# ATA.net
KiCad netlist of a schematic drawn in EAGLE
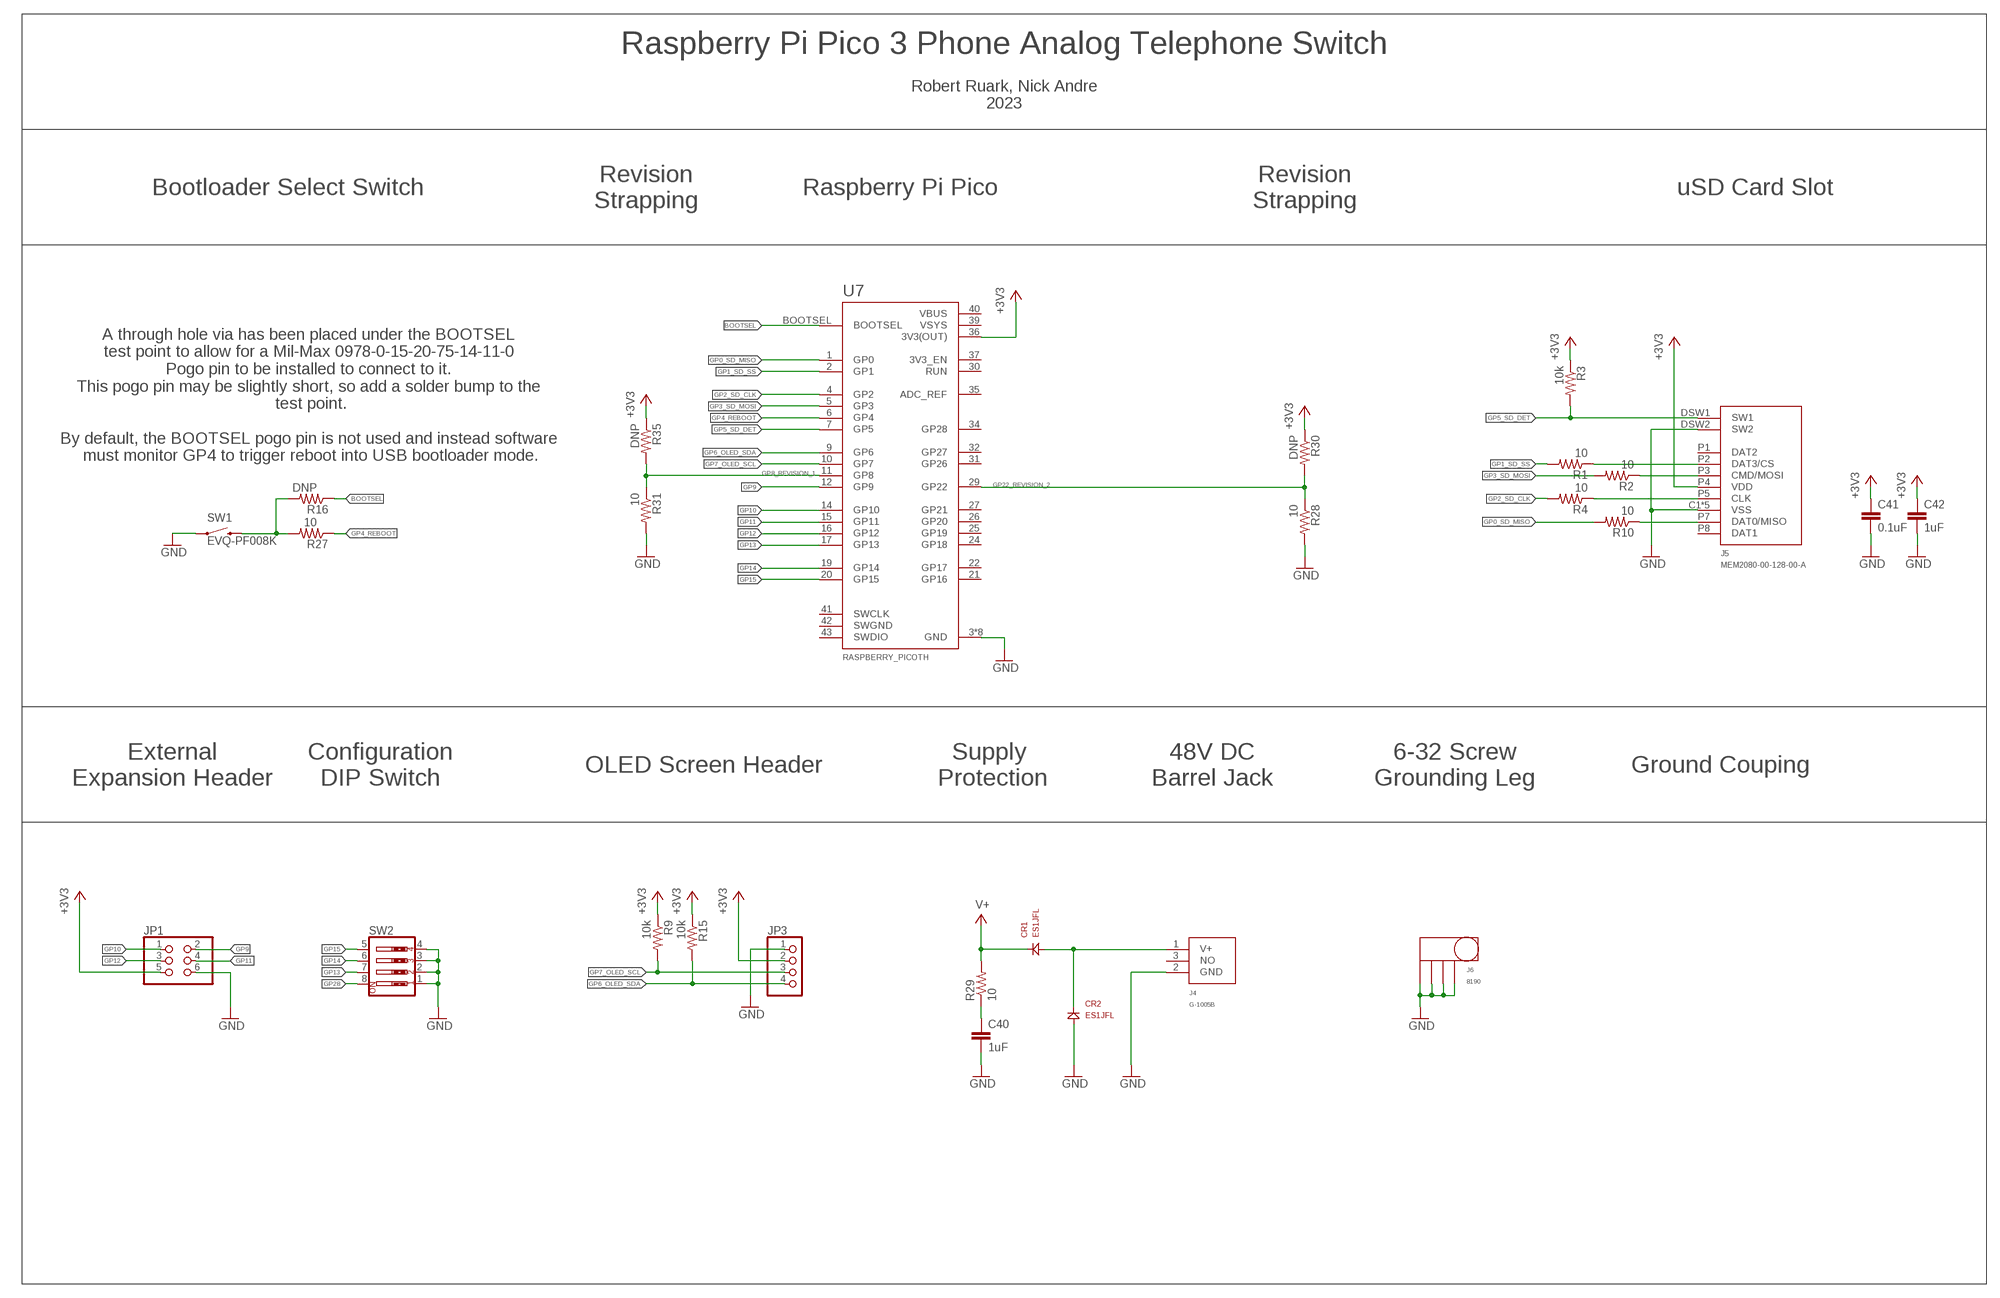
[diagram p0: schematic, sheet 1]
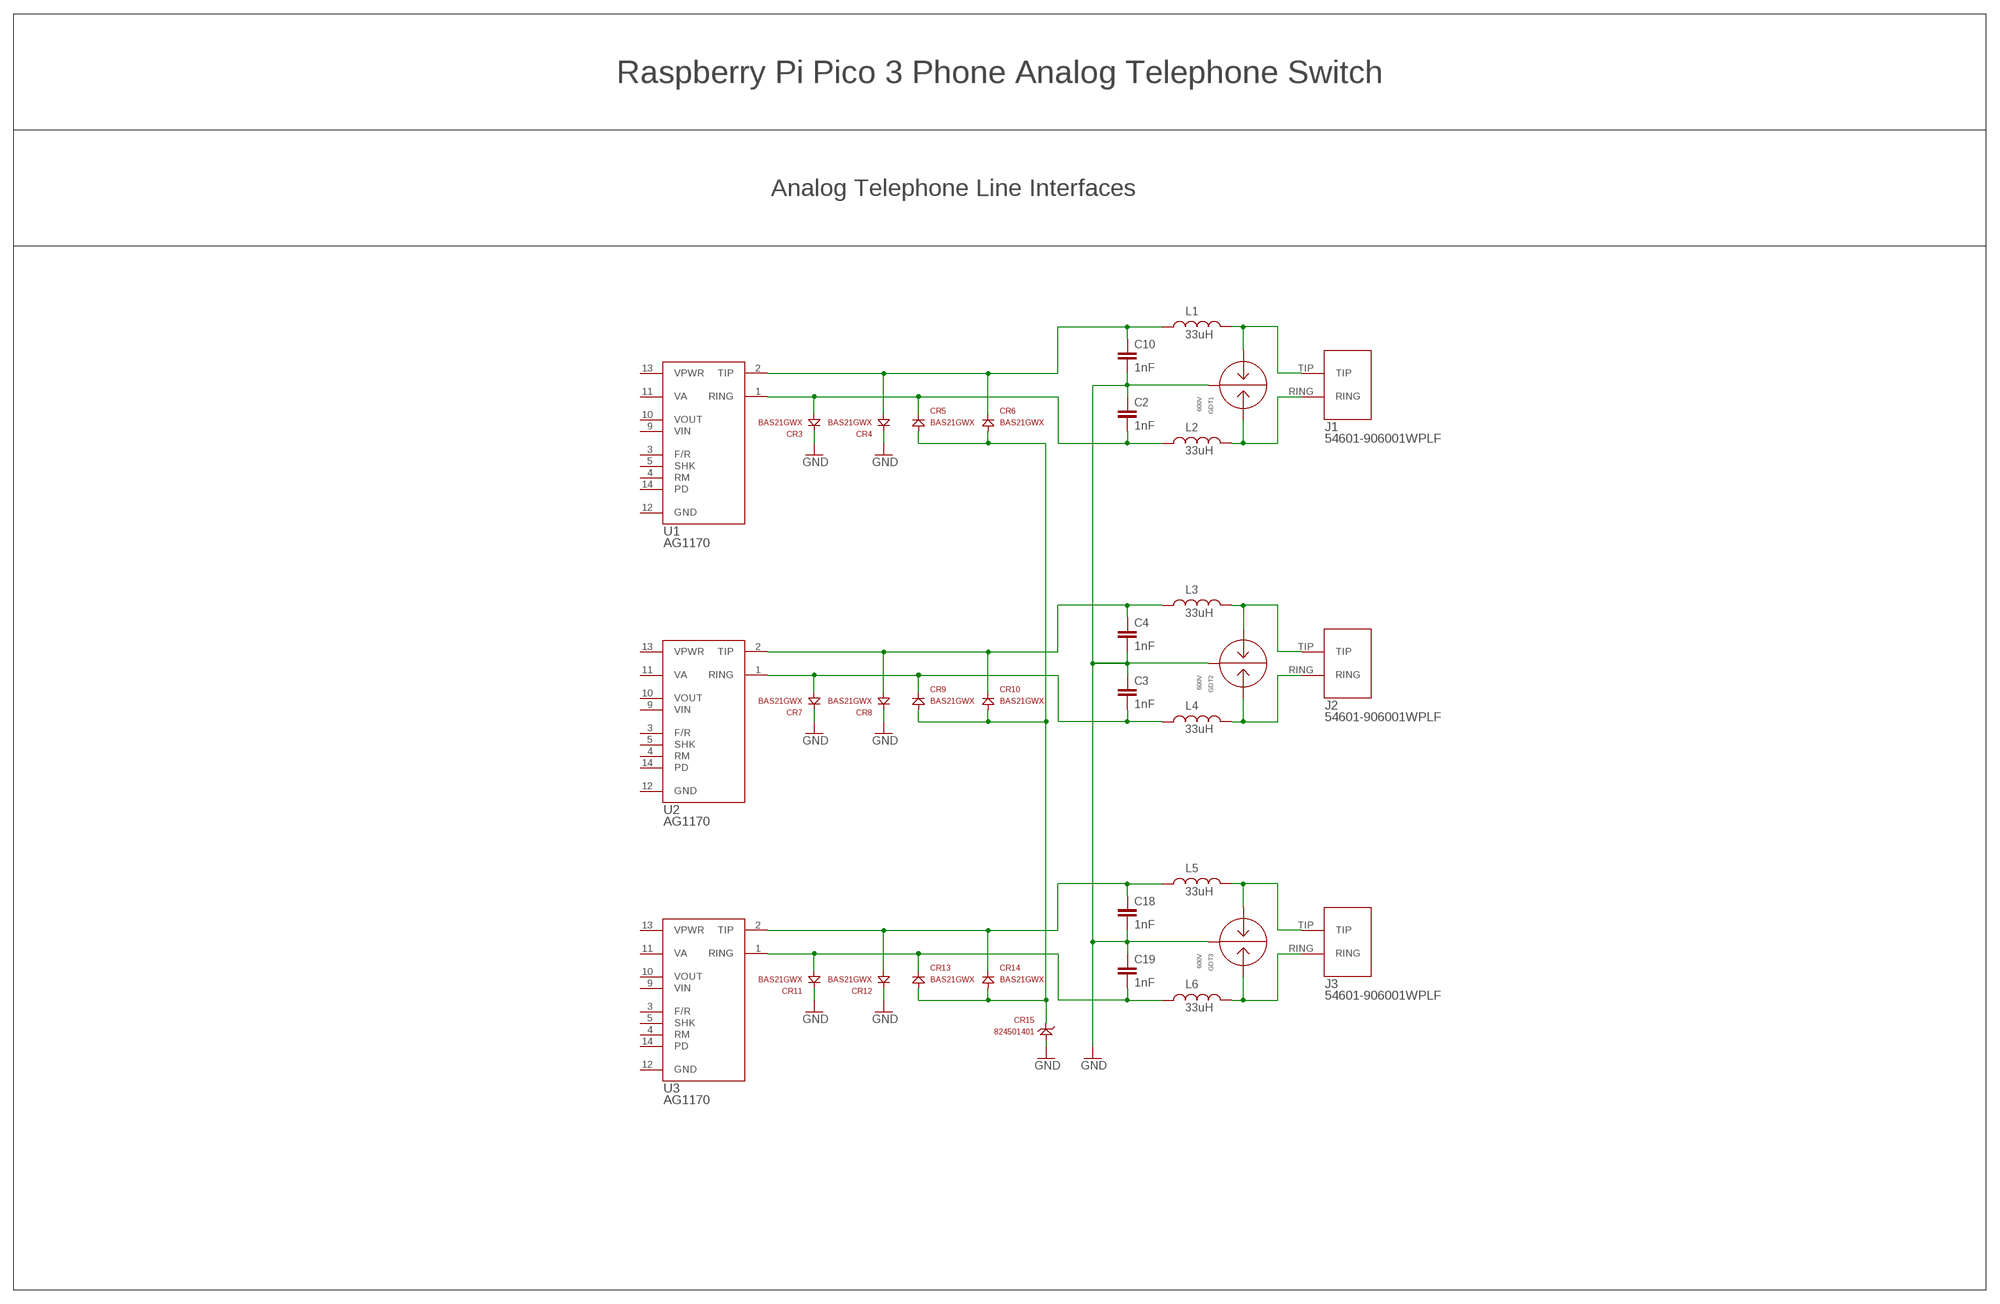
[diagram p1: schematic, sheet 2]

(export (version "E")
  (design (tool "Eeschema 10.0.6"))
  (components
    (comp (ref "C40")
      (value "1uF")
      (footprint "eagle-import:1206")
      (libsource (lib "eagle-import") (part "1206_CAPACITOR"))
    )
    (comp (ref "C41")
      (value "0.1uF")
      (footprint "eagle-import:0603")
      (libsource (lib "eagle-import") (part "0603_CAPACITOR"))
    )
    (comp (ref "C42")
      (value "1uF")
      (footprint "eagle-import:0805")
      (libsource (lib "eagle-import") (part "0805_CAPACITOR"))
    )
    (comp (ref "CR1")
      (value "ES1JFL")
      (footprint "eagle-import:SOD123(AK)")
      (fields (field (name "PARTNO") "ES1JFLCT-ND"))
      (libsource (lib "eagle-import") (part "ES1JFL"))
    )
    (comp (ref "CR2")
      (value "ES1JFL")
      (footprint "eagle-import:SOD123(AK)")
      (fields (field (name "PARTNO") "ES1JFLCT-ND"))
      (libsource (lib "eagle-import") (part "ES1JFL"))
    )
    (comp (ref "J4")
      (value "G-1005B")
      (footprint "eagle-import:G-1005B")
      (fields (field (name "PARTNO") "1939-G-1005B-ND"))
      (libsource (lib "eagle-import") (part "G-1005B"))
    )
    (comp (ref "J5")
      (value "MEM2080-00-128-00-A")
      (footprint "eagle-import:MEM2080")
      (fields (field (name "PARTNO") "2073-MEM2080-00-128-00-ACT-ND"))
      (libsource (lib "eagle-import") (part "MEM2080-00-128-00-A"))
    )
    (comp (ref "J6")
      (value "8190")
      (footprint "eagle-import:7781")
      (fields (field (name "PARTNO") "36-8190-ND"))
      (libsource (lib "eagle-import") (part "8190"))
    )
    (comp (ref "JP1")
      (value "PINHD-2X3/90")
      (footprint "eagle-import:2X03_90")
      (libsource (lib "eagle-import") (part "PINHD-2X3/90"))
    )
    (comp (ref "JP3")
      (value "PINHD-1X4")
      (footprint "eagle-import:1X04")
      (libsource (lib "eagle-import") (part "PINHD-1X4"))
    )
    (comp (ref "R1")
      (value "10")
      (footprint "eagle-import:0603")
      (libsource (lib "eagle-import") (part "0603_RESISTOR"))
    )
    (comp (ref "R2")
      (value "10")
      (footprint "eagle-import:0603")
      (libsource (lib "eagle-import") (part "0603_RESISTOR"))
    )
    (comp (ref "R3")
      (value "10k")
      (footprint "eagle-import:0603")
      (libsource (lib "eagle-import") (part "0603_RESISTOR"))
    )
    (comp (ref "R4")
      (value "10")
      (footprint "eagle-import:0603")
      (libsource (lib "eagle-import") (part "0603_RESISTOR"))
    )
    (comp (ref "R9")
      (value "10k")
      (footprint "eagle-import:0603")
      (libsource (lib "eagle-import") (part "0603_RESISTOR"))
    )
    (comp (ref "R10")
      (value "10")
      (footprint "eagle-import:0603")
      (libsource (lib "eagle-import") (part "0603_RESISTOR"))
    )
    (comp (ref "R15")
      (value "10k")
      (footprint "eagle-import:0603")
      (libsource (lib "eagle-import") (part "0603_RESISTOR"))
    )
    (comp (ref "R16")
      (value "DNP")
      (footprint "eagle-import:0603")
      (libsource (lib "eagle-import") (part "0603_RESISTOR"))
    )
    (comp (ref "R27")
      (value "10")
      (footprint "eagle-import:0603")
      (libsource (lib "eagle-import") (part "0603_RESISTOR"))
    )
    (comp (ref "R28")
      (value "10")
      (footprint "eagle-import:0603")
      (libsource (lib "eagle-import") (part "0603_RESISTOR"))
    )
    (comp (ref "R29")
      (value "10")
      (footprint "eagle-import:1206")
      (libsource (lib "eagle-import") (part "1206_RESISTOR"))
    )
    (comp (ref "R30")
      (value "DNP")
      (footprint "eagle-import:0603")
      (libsource (lib "eagle-import") (part "0603_RESISTOR"))
    )
    (comp (ref "R31")
      (value "10")
      (footprint "eagle-import:0603")
      (libsource (lib "eagle-import") (part "0603_RESISTOR"))
    )
    (comp (ref "R35")
      (value "DNP")
      (footprint "eagle-import:0603")
      (libsource (lib "eagle-import") (part "0603_RESISTOR"))
    )
    (comp (ref "SW1")
      (value "EVQ-PF008K")
      (footprint "eagle-import:EVQ-PF008K")
      (fields (field (name "PARTNO") "P10880S-ND"))
      (libsource (lib "eagle-import") (part "EVQ-PF008K"))
    )
    (comp (ref "SW2")
      (value "SW_DIP-4")
      (footprint "eagle-import:EDG-04")
      (libsource (lib "eagle-import") (part "SW_DIP-4"))
    )
    (comp (ref "U7")
      (value "RASPBERRY_PICOTH")
      (footprint "eagle-import:PICO-PKG-TH")
      (libsource (lib "eagle-import") (part "RASPBERRY_PICOTH"))
    )
    (comp (ref "C2")
      (value "1nF")
      (footprint "eagle-import:0805")
      (libsource (lib "eagle-import") (part "0805_CAPACITOR"))
    )
    (comp (ref "C3")
      (value "1nF")
      (footprint "eagle-import:0805")
      (libsource (lib "eagle-import") (part "0805_CAPACITOR"))
    )
    (comp (ref "C4")
      (value "1nF")
      (footprint "eagle-import:0805")
      (libsource (lib "eagle-import") (part "0805_CAPACITOR"))
    )
    (comp (ref "C10")
      (value "1nF")
      (footprint "eagle-import:0805")
      (libsource (lib "eagle-import") (part "0805_CAPACITOR"))
    )
    (comp (ref "C18")
      (value "1nF")
      (footprint "eagle-import:0805")
      (libsource (lib "eagle-import") (part "0805_CAPACITOR"))
    )
    (comp (ref "C19")
      (value "1nF")
      (footprint "eagle-import:0805")
      (libsource (lib "eagle-import") (part "0805_CAPACITOR"))
    )
    (comp (ref "CR3")
      (value "BAS21GWX")
      (footprint "eagle-import:SOD123")
      (fields (field (name "PARTNO") "1727-7323-1-ND"))
      (libsource (lib "eagle-import") (part "BAS21GWX"))
    )
    (comp (ref "CR4")
      (value "BAS21GWX")
      (footprint "eagle-import:SOD123")
      (fields (field (name "PARTNO") "1727-7323-1-ND"))
      (libsource (lib "eagle-import") (part "BAS21GWX"))
    )
    (comp (ref "CR5")
      (value "BAS21GWX")
      (footprint "eagle-import:SOD123")
      (fields (field (name "PARTNO") "1727-7323-1-ND"))
      (libsource (lib "eagle-import") (part "BAS21GWX"))
    )
    (comp (ref "CR6")
      (value "BAS21GWX")
      (footprint "eagle-import:SOD123")
      (fields (field (name "PARTNO") "1727-7323-1-ND"))
      (libsource (lib "eagle-import") (part "BAS21GWX"))
    )
    (comp (ref "CR7")
      (value "BAS21GWX")
      (footprint "eagle-import:SOD123")
      (fields (field (name "PARTNO") "1727-7323-1-ND"))
      (libsource (lib "eagle-import") (part "BAS21GWX"))
    )
    (comp (ref "CR8")
      (value "BAS21GWX")
      (footprint "eagle-import:SOD123")
      (fields (field (name "PARTNO") "1727-7323-1-ND"))
      (libsource (lib "eagle-import") (part "BAS21GWX"))
    )
    (comp (ref "CR9")
      (value "BAS21GWX")
      (footprint "eagle-import:SOD123")
      (fields (field (name "PARTNO") "1727-7323-1-ND"))
      (libsource (lib "eagle-import") (part "BAS21GWX"))
    )
    (comp (ref "CR10")
      (value "BAS21GWX")
      (footprint "eagle-import:SOD123")
      (fields (field (name "PARTNO") "1727-7323-1-ND"))
      (libsource (lib "eagle-import") (part "BAS21GWX"))
    )
    (comp (ref "CR11")
      (value "BAS21GWX")
      (footprint "eagle-import:SOD123")
      (fields (field (name "PARTNO") "1727-7323-1-ND"))
      (libsource (lib "eagle-import") (part "BAS21GWX"))
    )
    (comp (ref "CR12")
      (value "BAS21GWX")
      (footprint "eagle-import:SOD123")
      (fields (field (name "PARTNO") "1727-7323-1-ND"))
      (libsource (lib "eagle-import") (part "BAS21GWX"))
    )
    (comp (ref "CR13")
      (value "BAS21GWX")
      (footprint "eagle-import:SOD123")
      (fields (field (name "PARTNO") "1727-7323-1-ND"))
      (libsource (lib "eagle-import") (part "BAS21GWX"))
    )
    (comp (ref "CR14")
      (value "BAS21GWX")
      (footprint "eagle-import:SOD123")
      (fields (field (name "PARTNO") "1727-7323-1-ND"))
      (libsource (lib "eagle-import") (part "BAS21GWX"))
    )
    (comp (ref "CR15")
      (value "824501401")
      (footprint "eagle-import:DO-214AC")
      (fields (field (name "PARTNO") "732-9960-1-ND"))
      (libsource (lib "eagle-import") (part "824501401"))
    )
    (comp (ref "GDT1")
      (value "600V")
      (footprint "eagle-import:2036_GDT")
      (fields (field (name "PARTNO") "2036-60-SM-RPLFCT-ND"))
      (libsource (lib "eagle-import") (part "2036-60-SM-RPLF"))
    )
    (comp (ref "GDT2")
      (value "600V")
      (footprint "eagle-import:2036_GDT")
      (fields (field (name "PARTNO") "2036-60-SM-RPLFCT-ND"))
      (libsource (lib "eagle-import") (part "2036-60-SM-RPLF"))
    )
    (comp (ref "GDT3")
      (value "600V")
      (footprint "eagle-import:2036_GDT")
      (fields (field (name "PARTNO") "2036-60-SM-RPLFCT-ND"))
      (libsource (lib "eagle-import") (part "2036-60-SM-RPLF"))
    )
    (comp (ref "J1")
      (value "54601-906001WPLF")
      (footprint "eagle-import:54601-906001WPLF")
      (fields (field (name "PARTNO") "609-5354-ND"))
      (libsource (lib "eagle-import") (part "54601-906001WPLF"))
    )
    (comp (ref "J2")
      (value "54601-906001WPLF")
      (footprint "eagle-import:54601-906001WPLF")
      (fields (field (name "PARTNO") "609-5354-ND"))
      (libsource (lib "eagle-import") (part "54601-906001WPLF"))
    )
    (comp (ref "J3")
      (value "54601-906001WPLF")
      (footprint "eagle-import:54601-906001WPLF")
      (fields (field (name "PARTNO") "609-5354-ND"))
      (libsource (lib "eagle-import") (part "54601-906001WPLF"))
    )
    (comp (ref "L1")
      (value "33uH")
      (footprint "eagle-import:SDR0403")
      (fields (field (name "PARTNO") "SDR0403-330KLCT-ND"))
      (libsource (lib "eagle-import") (part "SDR0403-330KL"))
    )
    (comp (ref "L2")
      (value "33uH")
      (footprint "eagle-import:SDR0403")
      (fields (field (name "PARTNO") "SDR0403-330KLCT-ND"))
      (libsource (lib "eagle-import") (part "SDR0403-330KL"))
    )
    (comp (ref "L3")
      (value "33uH")
      (footprint "eagle-import:SDR0403")
      (fields (field (name "PARTNO") "SDR0403-330KLCT-ND"))
      (libsource (lib "eagle-import") (part "SDR0403-330KL"))
    )
    (comp (ref "L4")
      (value "33uH")
      (footprint "eagle-import:SDR0403")
      (fields (field (name "PARTNO") "SDR0403-330KLCT-ND"))
      (libsource (lib "eagle-import") (part "SDR0403-330KL"))
    )
    (comp (ref "L5")
      (value "33uH")
      (footprint "eagle-import:SDR0403")
      (fields (field (name "PARTNO") "SDR0403-330KLCT-ND"))
      (libsource (lib "eagle-import") (part "SDR0403-330KL"))
    )
    (comp (ref "L6")
      (value "33uH")
      (footprint "eagle-import:SDR0403")
      (fields (field (name "PARTNO") "SDR0403-330KLCT-ND"))
      (libsource (lib "eagle-import") (part "SDR0403-330KL"))
    )
    (comp (ref "U1")
      (value "AG1170")
      (footprint "eagle-import:AG1170S")
      (libsource (lib "eagle-import") (part "AG1170"))
    )
    (comp (ref "U2")
      (value "AG1170")
      (footprint "eagle-import:AG1170S")
      (libsource (lib "eagle-import") (part "AG1170"))
    )
    (comp (ref "U3")
      (value "AG1170")
      (footprint "eagle-import:AG1170S")
      (libsource (lib "eagle-import") (part "AG1170"))
    )
  )
  (nets
    (net (code "1") (name "+3V3") (class "Default")
      (node (ref "C41") (pin "1") (pinfunction "1_1") (pintype "passive"))
      (node (ref "C42") (pin "1") (pinfunction "1_1") (pintype "passive"))
      (node (ref "J5") (pin "P4") (pinfunction "VDD_P4") (pintype "bidirectional"))
      (node (ref "JP1") (pin "5") (pinfunction "5_5") (pintype "passive"))
      (node (ref "JP3") (pin "2") (pinfunction "2_2") (pintype "passive"))
      (node (ref "R15") (pin "1") (pinfunction "1_1") (pintype "passive"))
      (node (ref "R3") (pin "1") (pinfunction "1_1") (pintype "passive"))
      (node (ref "R30") (pin "1") (pinfunction "1_1") (pintype "passive"))
      (node (ref "R35") (pin "1") (pinfunction "1_1") (pintype "passive"))
      (node (ref "R9") (pin "1") (pinfunction "1_1") (pintype "passive"))
      (node (ref "U7") (pin "36") (pinfunction "3V3(OUT)_36") (pintype "power_in"))
    )
    (net (code "2") (name "BOOTSEL") (class "Default")
      (node (ref "R16") (pin "1") (pinfunction "1_1") (pintype "passive"))
      (node (ref "U7") (pin "BOOTSEL") (pinfunction "BOOTSEL_BOOTSEL") (pintype "bidirectional"))
    )
    (net (code "3") (name "GND") (class "Default")
      (node (ref "C10") (pin "2") (pinfunction "2_2") (pintype "passive"))
      (node (ref "C18") (pin "2") (pinfunction "2_2") (pintype "passive"))
      (node (ref "C19") (pin "1") (pinfunction "1_1") (pintype "passive"))
      (node (ref "C2") (pin "1") (pinfunction "1_1") (pintype "passive"))
      (node (ref "C3") (pin "1") (pinfunction "1_1") (pintype "passive"))
      (node (ref "C4") (pin "2") (pinfunction "2_2") (pintype "passive"))
      (node (ref "C40") (pin "2") (pinfunction "2_2") (pintype "passive"))
      (node (ref "C41") (pin "2") (pinfunction "2_2") (pintype "passive"))
      (node (ref "C42") (pin "2") (pinfunction "2_2") (pintype "passive"))
      (node (ref "CR11") (pin "1") (pinfunction "K_1") (pintype "bidirectional"))
      (node (ref "CR12") (pin "1") (pinfunction "K_1") (pintype "bidirectional"))
      (node (ref "CR15") (pin "A") (pinfunction "A_A") (pintype "bidirectional"))
      (node (ref "CR2") (pin "A") (pinfunction "A_A") (pintype "bidirectional"))
      (node (ref "CR3") (pin "1") (pinfunction "K_1") (pintype "bidirectional"))
      (node (ref "CR4") (pin "1") (pinfunction "K_1") (pintype "bidirectional"))
      (node (ref "CR7") (pin "1") (pinfunction "K_1") (pintype "bidirectional"))
      (node (ref "CR8") (pin "1") (pinfunction "K_1") (pintype "bidirectional"))
      (node (ref "GDT1") (pin "C") (pinfunction "C_C") (pintype "bidirectional"))
      (node (ref "GDT2") (pin "C") (pinfunction "C_C") (pintype "bidirectional"))
      (node (ref "GDT3") (pin "C") (pinfunction "C_C") (pintype "bidirectional"))
      (node (ref "J4") (pin "2") (pinfunction "GND_2") (pintype "bidirectional"))
      (node (ref "J5") (pin "C1") (pinfunction "VSS_C1") (pintype "bidirectional"))
      (node (ref "J5") (pin "C2") (pinfunction "VSS_C2") (pintype "bidirectional"))
      (node (ref "J5") (pin "C3") (pinfunction "VSS_C3") (pintype "bidirectional"))
      (node (ref "J5") (pin "C4") (pinfunction "VSS_C4") (pintype "bidirectional"))
      (node (ref "J5") (pin "DSW2") (pinfunction "SW2_DSW2") (pintype "bidirectional"))
      (node (ref "J5") (pin "P6") (pinfunction "VSS_P6") (pintype "bidirectional"))
      (node (ref "J6") (pin "P$1") (pinfunction "P$1_P$1") (pintype "bidirectional"))
      (node (ref "J6") (pin "P$2") (pinfunction "P$2_P$2") (pintype "bidirectional"))
      (node (ref "J6") (pin "P$3") (pinfunction "P$3_P$3") (pintype "bidirectional"))
      (node (ref "J6") (pin "P$4") (pinfunction "P$4_P$4") (pintype "bidirectional"))
      (node (ref "JP1") (pin "6") (pinfunction "6_6") (pintype "passive"))
      (node (ref "JP3") (pin "1") (pinfunction "1_1") (pintype "passive"))
      (node (ref "R28") (pin "2") (pinfunction "2_2") (pintype "passive"))
      (node (ref "R31") (pin "2") (pinfunction "2_2") (pintype "passive"))
      (node (ref "SW1") (pin "S1") (pinfunction "1_S1") (pintype "passive"))
      (node (ref "SW2") (pin "1") (pinfunction "1_1") (pintype "passive"))
      (node (ref "SW2") (pin "2") (pinfunction "2_2") (pintype "passive"))
      (node (ref "SW2") (pin "3") (pinfunction "3_3") (pintype "passive"))
      (node (ref "SW2") (pin "4") (pinfunction "4_4") (pintype "passive"))
      (node (ref "U7") (pin "13") (pinfunction "GND_13") (pintype "power_in"))
      (node (ref "U7") (pin "18") (pinfunction "GND_18") (pintype "power_in"))
      (node (ref "U7") (pin "23") (pinfunction "GND_23") (pintype "power_in"))
      (node (ref "U7") (pin "28") (pinfunction "GND_28") (pintype "power_in"))
      (node (ref "U7") (pin "3") (pinfunction "GND_3") (pintype "power_in"))
      (node (ref "U7") (pin "33") (pinfunction "GND_33") (pintype "power_in"))
      (node (ref "U7") (pin "38") (pinfunction "GND_38") (pintype "power_in"))
      (node (ref "U7") (pin "8") (pinfunction "GND_8") (pintype "power_in"))
    )
    (net (code "4") (name "GP0_SD_MISO") (class "Default")
      (node (ref "R10") (pin "2") (pinfunction "2_2") (pintype "passive"))
      (node (ref "U7") (pin "1") (pinfunction "GP0_1") (pintype "bidirectional"))
    )
    (net (code "5") (name "GP1_SD_SS") (class "Default")
      (node (ref "R1") (pin "2") (pinfunction "2_2") (pintype "passive"))
      (node (ref "U7") (pin "2") (pinfunction "GP1_2") (pintype "bidirectional"))
    )
    (net (code "6") (name "GP2_SD_CLK") (class "Default")
      (node (ref "R4") (pin "2") (pinfunction "2_2") (pintype "passive"))
      (node (ref "U7") (pin "4") (pinfunction "GP2_4") (pintype "bidirectional"))
    )
    (net (code "7") (name "GP3_SD_MOSI") (class "Default")
      (node (ref "R2") (pin "2") (pinfunction "2_2") (pintype "passive"))
      (node (ref "U7") (pin "5") (pinfunction "GP3_5") (pintype "bidirectional"))
    )
    (net (code "8") (name "GP4_REBOOT") (class "Default")
      (node (ref "R27") (pin "1") (pinfunction "1_1") (pintype "passive"))
      (node (ref "U7") (pin "6") (pinfunction "GP4_6") (pintype "bidirectional"))
    )
    (net (code "9") (name "GP5_SD_DET") (class "Default")
      (node (ref "J5") (pin "DSW1") (pinfunction "SW1_DSW1") (pintype "bidirectional"))
      (node (ref "R3") (pin "2") (pinfunction "2_2") (pintype "passive"))
      (node (ref "U7") (pin "7") (pinfunction "GP5_7") (pintype "bidirectional"))
    )
    (net (code "10") (name "GP6_OLED_SDA") (class "Default")
      (node (ref "JP3") (pin "4") (pinfunction "4_4") (pintype "passive"))
      (node (ref "R15") (pin "2") (pinfunction "2_2") (pintype "passive"))
      (node (ref "U7") (pin "9") (pinfunction "GP6_9") (pintype "bidirectional"))
    )
    (net (code "11") (name "GP7_OLED_SCL") (class "Default")
      (node (ref "JP3") (pin "3") (pinfunction "3_3") (pintype "passive"))
      (node (ref "R9") (pin "2") (pinfunction "2_2") (pintype "passive"))
      (node (ref "U7") (pin "10") (pinfunction "GP7_10") (pintype "bidirectional"))
    )
    (net (code "12") (name "GP8_REVISION_1") (class "Default")
      (node (ref "R31") (pin "1") (pinfunction "1_1") (pintype "passive"))
      (node (ref "R35") (pin "2") (pinfunction "2_2") (pintype "passive"))
      (node (ref "U7") (pin "11") (pinfunction "GP8_11") (pintype "bidirectional"))
    )
    (net (code "13") (name "GP9") (class "Default")
      (node (ref "JP1") (pin "2") (pinfunction "2_2") (pintype "passive"))
      (node (ref "U7") (pin "12") (pinfunction "GP9_12") (pintype "bidirectional"))
    )
    (net (code "14") (name "GP10") (class "Default")
      (node (ref "JP1") (pin "1") (pinfunction "1_1") (pintype "passive"))
      (node (ref "U7") (pin "14") (pinfunction "GP10_14") (pintype "bidirectional"))
    )
    (net (code "15") (name "GP11") (class "Default")
      (node (ref "JP1") (pin "4") (pinfunction "4_4") (pintype "passive"))
      (node (ref "U7") (pin "15") (pinfunction "GP11_15") (pintype "bidirectional"))
    )
    (net (code "16") (name "GP12") (class "Default")
      (node (ref "JP1") (pin "3") (pinfunction "3_3") (pintype "passive"))
      (node (ref "U7") (pin "16") (pinfunction "GP12_16") (pintype "bidirectional"))
    )
    (net (code "17") (name "GP13") (class "Default")
      (node (ref "SW2") (pin "7") (pinfunction "7_7") (pintype "passive"))
      (node (ref "U7") (pin "17") (pinfunction "GP13_17") (pintype "bidirectional"))
    )
    (net (code "18") (name "GP14") (class "Default")
      (node (ref "SW2") (pin "6") (pinfunction "6_6") (pintype "passive"))
      (node (ref "U7") (pin "19") (pinfunction "GP14_19") (pintype "bidirectional"))
    )
    (net (code "19") (name "GP15") (class "Default")
      (node (ref "SW2") (pin "5") (pinfunction "5_5") (pintype "passive"))
      (node (ref "U7") (pin "20") (pinfunction "GP15_20") (pintype "bidirectional"))
    )
    (net (code "20") (name "GP22_REVISION_2") (class "Default")
      (node (ref "R28") (pin "1") (pinfunction "1_1") (pintype "passive"))
      (node (ref "R30") (pin "2") (pinfunction "2_2") (pintype "passive"))
      (node (ref "U7") (pin "29") (pinfunction "GP22_29") (pintype "bidirectional"))
    )
    (net (code "21") (name "GP28") (class "Default")
      (node (ref "SW2") (pin "8") (pinfunction "8_8") (pintype "passive"))
    )
    (net (code "22") (name "Net-(C40-Pad1)") (class "Default")
      (node (ref "C40") (pin "1") (pinfunction "1_1") (pintype "passive"))
      (node (ref "R29") (pin "1") (pinfunction "1_1") (pintype "passive"))
    )
    (net (code "23") (name "Net-(CR3-A)") (class "Default")
      (node (ref "C2") (pin "2") (pinfunction "2_2") (pintype "passive"))
      (node (ref "CR3") (pin "2") (pinfunction "A_2") (pintype "bidirectional"))
      (node (ref "CR5") (pin "1") (pinfunction "K_1") (pintype "bidirectional"))
      (node (ref "L2") (pin "1") (pinfunction "P$1_1") (pintype "bidirectional"))
      (node (ref "U1") (pin "1") (pinfunction "RING_1") (pintype "bidirectional"))
    )
    (net (code "24") (name "Net-(CR4-A)") (class "Default")
      (node (ref "C10") (pin "1") (pinfunction "1_1") (pintype "passive"))
      (node (ref "CR4") (pin "2") (pinfunction "A_2") (pintype "bidirectional"))
      (node (ref "CR6") (pin "1") (pinfunction "K_1") (pintype "bidirectional"))
      (node (ref "L1") (pin "1") (pinfunction "P$1_1") (pintype "bidirectional"))
      (node (ref "U1") (pin "2") (pinfunction "TIP_2") (pintype "bidirectional"))
    )
    (net (code "25") (name "Net-(CR7-A)") (class "Default")
      (node (ref "C3") (pin "2") (pinfunction "2_2") (pintype "passive"))
      (node (ref "CR7") (pin "2") (pinfunction "A_2") (pintype "bidirectional"))
      (node (ref "CR9") (pin "1") (pinfunction "K_1") (pintype "bidirectional"))
      (node (ref "L4") (pin "1") (pinfunction "P$1_1") (pintype "bidirectional"))
      (node (ref "U2") (pin "1") (pinfunction "RING_1") (pintype "bidirectional"))
    )
    (net (code "26") (name "Net-(CR10-A)") (class "Default")
      (node (ref "CR10") (pin "2") (pinfunction "A_2") (pintype "bidirectional"))
      (node (ref "CR13") (pin "2") (pinfunction "A_2") (pintype "bidirectional"))
      (node (ref "CR14") (pin "2") (pinfunction "A_2") (pintype "bidirectional"))
      (node (ref "CR15") (pin "C") (pinfunction "K_C") (pintype "bidirectional"))
      (node (ref "CR5") (pin "2") (pinfunction "A_2") (pintype "bidirectional"))
      (node (ref "CR6") (pin "2") (pinfunction "A_2") (pintype "bidirectional"))
      (node (ref "CR9") (pin "2") (pinfunction "A_2") (pintype "bidirectional"))
    )
    (net (code "27") (name "Net-(CR10-K)") (class "Default")
      (node (ref "C4") (pin "1") (pinfunction "1_1") (pintype "passive"))
      (node (ref "CR10") (pin "1") (pinfunction "K_1") (pintype "bidirectional"))
      (node (ref "CR8") (pin "2") (pinfunction "A_2") (pintype "bidirectional"))
      (node (ref "L3") (pin "1") (pinfunction "P$1_1") (pintype "bidirectional"))
      (node (ref "U2") (pin "2") (pinfunction "TIP_2") (pintype "bidirectional"))
    )
    (net (code "28") (name "Net-(CR11-A)") (class "Default")
      (node (ref "C19") (pin "2") (pinfunction "2_2") (pintype "passive"))
      (node (ref "CR11") (pin "2") (pinfunction "A_2") (pintype "bidirectional"))
      (node (ref "CR13") (pin "1") (pinfunction "K_1") (pintype "bidirectional"))
      (node (ref "L6") (pin "1") (pinfunction "P$1_1") (pintype "bidirectional"))
      (node (ref "U3") (pin "1") (pinfunction "RING_1") (pintype "bidirectional"))
    )
    (net (code "29") (name "Net-(CR12-A)") (class "Default")
      (node (ref "C18") (pin "1") (pinfunction "1_1") (pintype "passive"))
      (node (ref "CR12") (pin "2") (pinfunction "A_2") (pintype "bidirectional"))
      (node (ref "CR14") (pin "1") (pinfunction "K_1") (pintype "bidirectional"))
      (node (ref "L5") (pin "1") (pinfunction "P$1_1") (pintype "bidirectional"))
      (node (ref "U3") (pin "2") (pinfunction "TIP_2") (pintype "bidirectional"))
    )
    (net (code "30") (name "Net-(J4-V+)") (class "Default")
      (node (ref "CR1") (pin "A") (pinfunction "A_A") (pintype "bidirectional"))
      (node (ref "CR2") (pin "K") (pinfunction "K_K") (pintype "bidirectional"))
      (node (ref "J4") (pin "1") (pinfunction "V+_1") (pintype "bidirectional"))
    )
    (net (code "31") (name "Net-(J5-CLK)") (class "Default")
      (node (ref "J5") (pin "P5") (pinfunction "CLK_P5") (pintype "bidirectional"))
      (node (ref "R4") (pin "1") (pinfunction "1_1") (pintype "passive"))
    )
    (net (code "32") (name "Net-(J5-CMD{slash}MOSI)") (class "Default")
      (node (ref "J5") (pin "P3") (pinfunction "CMD/MOSI_P3") (pintype "bidirectional"))
      (node (ref "R2") (pin "1") (pinfunction "1_1") (pintype "passive"))
    )
    (net (code "33") (name "Net-(J5-DAT0{slash}MISO)") (class "Default")
      (node (ref "J5") (pin "P7") (pinfunction "DAT0/MISO_P7") (pintype "bidirectional"))
      (node (ref "R10") (pin "1") (pinfunction "1_1") (pintype "passive"))
    )
    (net (code "34") (name "Net-(J5-DAT3{slash}CS)") (class "Default")
      (node (ref "J5") (pin "P2") (pinfunction "DAT3/CS_P2") (pintype "bidirectional"))
      (node (ref "R1") (pin "1") (pinfunction "1_1") (pintype "passive"))
    )
    (net (code "35") (name "Net-(L1-P$2)") (class "Default")
      (node (ref "GDT1") (pin "L1") (pinfunction "L1_L1") (pintype "bidirectional"))
      (node (ref "J1") (pin "TIP") (pinfunction "TIP_TIP") (pintype "bidirectional"))
      (node (ref "L1") (pin "2") (pinfunction "P$2_2") (pintype "bidirectional"))
    )
    (net (code "36") (name "Net-(L2-P$2)") (class "Default")
      (node (ref "GDT1") (pin "L2") (pinfunction "L2_L2") (pintype "bidirectional"))
      (node (ref "J1") (pin "RING") (pinfunction "RING_RING") (pintype "bidirectional"))
      (node (ref "L2") (pin "2") (pinfunction "P$2_2") (pintype "bidirectional"))
    )
    (net (code "37") (name "Net-(L3-P$2)") (class "Default")
      (node (ref "GDT2") (pin "L1") (pinfunction "L1_L1") (pintype "bidirectional"))
      (node (ref "J2") (pin "TIP") (pinfunction "TIP_TIP") (pintype "bidirectional"))
      (node (ref "L3") (pin "2") (pinfunction "P$2_2") (pintype "bidirectional"))
    )
    (net (code "38") (name "Net-(L4-P$2)") (class "Default")
      (node (ref "GDT2") (pin "L2") (pinfunction "L2_L2") (pintype "bidirectional"))
      (node (ref "J2") (pin "RING") (pinfunction "RING_RING") (pintype "bidirectional"))
      (node (ref "L4") (pin "2") (pinfunction "P$2_2") (pintype "bidirectional"))
    )
    (net (code "39") (name "Net-(L5-P$2)") (class "Default")
      (node (ref "GDT3") (pin "L1") (pinfunction "L1_L1") (pintype "bidirectional"))
      (node (ref "J3") (pin "TIP") (pinfunction "TIP_TIP") (pintype "bidirectional"))
      (node (ref "L5") (pin "2") (pinfunction "P$2_2") (pintype "bidirectional"))
    )
    (net (code "40") (name "Net-(L6-P$2)") (class "Default")
      (node (ref "GDT3") (pin "L2") (pinfunction "L2_L2") (pintype "bidirectional"))
      (node (ref "J3") (pin "RING") (pinfunction "RING_RING") (pintype "bidirectional"))
      (node (ref "L6") (pin "2") (pinfunction "P$2_2") (pintype "bidirectional"))
    )
    (net (code "41") (name "Net-(SW1-2)") (class "Default")
      (node (ref "R16") (pin "2") (pinfunction "2_2") (pintype "passive"))
      (node (ref "R27") (pin "2") (pinfunction "2_2") (pintype "passive"))
      (node (ref "SW1") (pin "S2") (pinfunction "2_S2") (pintype "passive"))
    )
    (net (code "42") (name "SWGND") (class "Default")
      (node (ref "U7") (pin "42") (pinfunction "SWGND_42") (pintype "power_in"))
    )
    (net (code "43") (name "V+") (class "Default")
      (node (ref "CR1") (pin "K") (pinfunction "K_K") (pintype "bidirectional"))
      (node (ref "R29") (pin "2") (pinfunction "2_2") (pintype "passive"))
    )
    (net (code "44") (name "VBUS") (class "Default")
      (node (ref "U7") (pin "40") (pinfunction "VBUS_40") (pintype "power_in"))
    )
    (net (code "45") (name "VSYS") (class "Default")
      (node (ref "U7") (pin "39") (pinfunction "VSYS_39") (pintype "power_in"))
    )
    (net (code "46") (name "unconnected-(J4-NO-Pad3)") (class "Default")
      (node (ref "J4") (pin "3") (pinfunction "NO_3") (pintype "bidirectional"))
    )
    (net (code "47") (name "unconnected-(J5-DAT1-PadP8)") (class "Default")
      (node (ref "J5") (pin "P8") (pinfunction "DAT1_P8") (pintype "bidirectional"))
    )
    (net (code "48") (name "unconnected-(J5-DAT2-PadP1)") (class "Default")
      (node (ref "J5") (pin "P1") (pinfunction "DAT2_P1") (pintype "bidirectional"))
    )
    (net (code "49") (name "unconnected-(U1-F{slash}R-Pad3)") (class "Default")
      (node (ref "U1") (pin "3") (pinfunction "F/R_3") (pintype "bidirectional"))
    )
    (net (code "50") (name "unconnected-(U1-GND-Pad12)") (class "Default")
      (node (ref "U1") (pin "12") (pinfunction "GND_12") (pintype "bidirectional"))
    )
    (net (code "51") (name "unconnected-(U1-PD-Pad14)") (class "Default")
      (node (ref "U1") (pin "14") (pinfunction "PD_14") (pintype "bidirectional"))
    )
    (net (code "52") (name "unconnected-(U1-RM-Pad4)") (class "Default")
      (node (ref "U1") (pin "4") (pinfunction "RM_4") (pintype "bidirectional"))
    )
    (net (code "53") (name "unconnected-(U1-SHK-Pad5)") (class "Default")
      (node (ref "U1") (pin "5") (pinfunction "SHK_5") (pintype "bidirectional"))
    )
    (net (code "54") (name "unconnected-(U1-VA-Pad11)") (class "Default")
      (node (ref "U1") (pin "11") (pinfunction "VA_11") (pintype "bidirectional"))
    )
    (net (code "55") (name "unconnected-(U1-VIN-Pad9)") (class "Default")
      (node (ref "U1") (pin "9") (pinfunction "VIN_9") (pintype "bidirectional"))
    )
    (net (code "56") (name "unconnected-(U1-VOUT-Pad10)") (class "Default")
      (node (ref "U1") (pin "10") (pinfunction "VOUT_10") (pintype "bidirectional"))
    )
    (net (code "57") (name "unconnected-(U1-VPWR-Pad13)") (class "Default")
      (node (ref "U1") (pin "13") (pinfunction "VPWR_13") (pintype "bidirectional"))
    )
    (net (code "58") (name "unconnected-(U2-F{slash}R-Pad3)") (class "Default")
      (node (ref "U2") (pin "3") (pinfunction "F/R_3") (pintype "bidirectional"))
    )
    (net (code "59") (name "unconnected-(U2-GND-Pad12)") (class "Default")
      (node (ref "U2") (pin "12") (pinfunction "GND_12") (pintype "bidirectional"))
    )
    (net (code "60") (name "unconnected-(U2-PD-Pad14)") (class "Default")
      (node (ref "U2") (pin "14") (pinfunction "PD_14") (pintype "bidirectional"))
    )
    (net (code "61") (name "unconnected-(U2-RM-Pad4)") (class "Default")
      (node (ref "U2") (pin "4") (pinfunction "RM_4") (pintype "bidirectional"))
    )
    (net (code "62") (name "unconnected-(U2-SHK-Pad5)") (class "Default")
      (node (ref "U2") (pin "5") (pinfunction "SHK_5") (pintype "bidirectional"))
    )
    (net (code "63") (name "unconnected-(U2-VA-Pad11)") (class "Default")
      (node (ref "U2") (pin "11") (pinfunction "VA_11") (pintype "bidirectional"))
    )
    (net (code "64") (name "unconnected-(U2-VIN-Pad9)") (class "Default")
      (node (ref "U2") (pin "9") (pinfunction "VIN_9") (pintype "bidirectional"))
    )
    (net (code "65") (name "unconnected-(U2-VOUT-Pad10)") (class "Default")
      (node (ref "U2") (pin "10") (pinfunction "VOUT_10") (pintype "bidirectional"))
    )
    (net (code "66") (name "unconnected-(U2-VPWR-Pad13)") (class "Default")
      (node (ref "U2") (pin "13") (pinfunction "VPWR_13") (pintype "bidirectional"))
    )
    (net (code "67") (name "unconnected-(U3-F{slash}R-Pad3)") (class "Default")
      (node (ref "U3") (pin "3") (pinfunction "F/R_3") (pintype "bidirectional"))
    )
    (net (code "68") (name "unconnected-(U3-GND-Pad12)") (class "Default")
      (node (ref "U3") (pin "12") (pinfunction "GND_12") (pintype "bidirectional"))
    )
    (net (code "69") (name "unconnected-(U3-PD-Pad14)") (class "Default")
      (node (ref "U3") (pin "14") (pinfunction "PD_14") (pintype "bidirectional"))
    )
    (net (code "70") (name "unconnected-(U3-RM-Pad4)") (class "Default")
      (node (ref "U3") (pin "4") (pinfunction "RM_4") (pintype "bidirectional"))
    )
    (net (code "71") (name "unconnected-(U3-SHK-Pad5)") (class "Default")
      (node (ref "U3") (pin "5") (pinfunction "SHK_5") (pintype "bidirectional"))
    )
    (net (code "72") (name "unconnected-(U3-VA-Pad11)") (class "Default")
      (node (ref "U3") (pin "11") (pinfunction "VA_11") (pintype "bidirectional"))
    )
    (net (code "73") (name "unconnected-(U3-VIN-Pad9)") (class "Default")
      (node (ref "U3") (pin "9") (pinfunction "VIN_9") (pintype "bidirectional"))
    )
    (net (code "74") (name "unconnected-(U3-VOUT-Pad10)") (class "Default")
      (node (ref "U3") (pin "10") (pinfunction "VOUT_10") (pintype "bidirectional"))
    )
    (net (code "75") (name "unconnected-(U3-VPWR-Pad13)") (class "Default")
      (node (ref "U3") (pin "13") (pinfunction "VPWR_13") (pintype "bidirectional"))
    )
    (net (code "76") (name "unconnected-(U7-3V3_EN-Pad37)") (class "Default")
      (node (ref "U7") (pin "37") (pinfunction "3V3_EN_37") (pintype "input"))
    )
    (net (code "77") (name "unconnected-(U7-ADC_REF-Pad35)") (class "Default")
      (node (ref "U7") (pin "35") (pinfunction "ADC_REF_35") (pintype "input"))
    )
    (net (code "78") (name "unconnected-(U7-GP16-Pad21)") (class "Default")
      (node (ref "U7") (pin "21") (pinfunction "GP16_21") (pintype "bidirectional"))
    )
    (net (code "79") (name "unconnected-(U7-GP17-Pad22)") (class "Default")
      (node (ref "U7") (pin "22") (pinfunction "GP17_22") (pintype "bidirectional"))
    )
    (net (code "80") (name "unconnected-(U7-GP18-Pad24)") (class "Default")
      (node (ref "U7") (pin "24") (pinfunction "GP18_24") (pintype "bidirectional"))
    )
    (net (code "81") (name "unconnected-(U7-GP19-Pad25)") (class "Default")
      (node (ref "U7") (pin "25") (pinfunction "GP19_25") (pintype "bidirectional"))
    )
    (net (code "82") (name "unconnected-(U7-GP20-Pad26)") (class "Default")
      (node (ref "U7") (pin "26") (pinfunction "GP20_26") (pintype "bidirectional"))
    )
    (net (code "83") (name "unconnected-(U7-GP21-Pad27)") (class "Default")
      (node (ref "U7") (pin "27") (pinfunction "GP21_27") (pintype "bidirectional"))
    )
    (net (code "84") (name "unconnected-(U7-GP26-Pad31)") (class "Default")
      (node (ref "U7") (pin "31") (pinfunction "GP26_31") (pintype "bidirectional"))
    )
    (net (code "85") (name "unconnected-(U7-GP27-Pad32)") (class "Default")
      (node (ref "U7") (pin "32") (pinfunction "GP27_32") (pintype "bidirectional"))
    )
    (net (code "86") (name "unconnected-(U7-GP28-Pad34)") (class "Default")
      (node (ref "U7") (pin "34") (pinfunction "GP28_34") (pintype "bidirectional"))
    )
    (net (code "87") (name "unconnected-(U7-RUN-Pad30)") (class "Default")
      (node (ref "U7") (pin "30") (pinfunction "RUN_30") (pintype "input"))
    )
    (net (code "88") (name "unconnected-(U7-SWCLK-Pad41)") (class "Default")
      (node (ref "U7") (pin "41") (pinfunction "SWCLK_41") (pintype "input"))
    )
    (net (code "89") (name "unconnected-(U7-SWDIO-Pad43)") (class "Default")
      (node (ref "U7") (pin "43") (pinfunction "SWDIO_43") (pintype "bidirectional"))
    )
  )
)
